# proto_secondaire.net
KiCad netlist of a schematic drawn in EAGLE
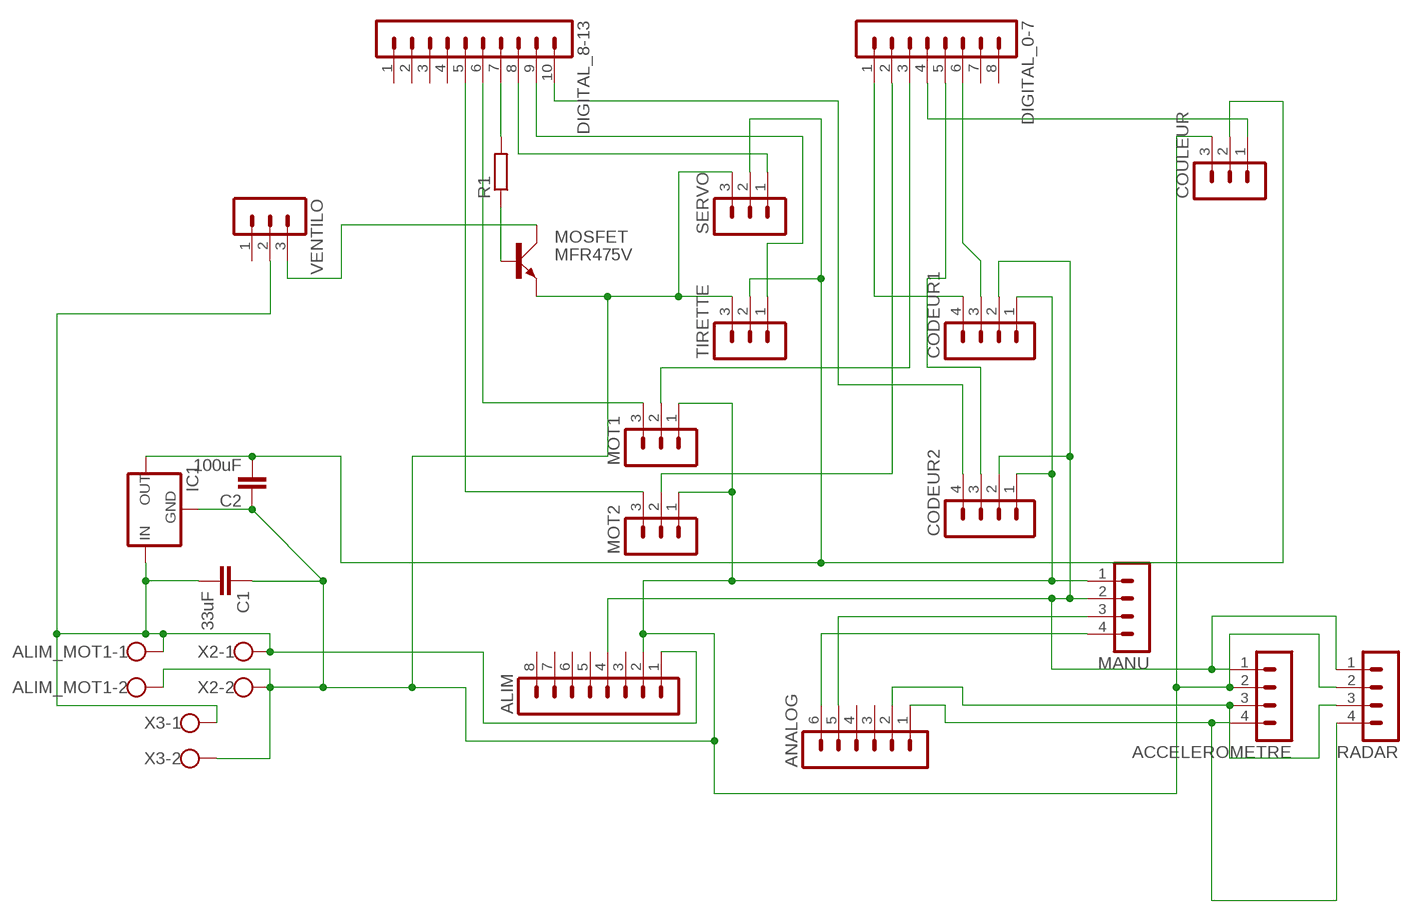
[diagram p0: schematic, sheet 1]

(export (version "E")
  (design (tool "Eeschema 10.0.6"))
  (components
    (comp (ref "ACCELEROMETRE")
      (value "MA04-1")
      (footprint "eagle-import:MA04-1")
      (libsource (lib "eagle-import") (part "MA04-1"))
    )
    (comp (ref "ALIM")
      (value "MA08-1")
      (footprint "eagle-import:MA08-1")
      (libsource (lib "eagle-import") (part "MA08-1"))
    )
    (comp (ref "ALIM_MOT1")
      (value "W237-102")
      (footprint "eagle-import:W237-102")
      (fields (field (name "MPN") "237-102"))
      (libsource (lib "eagle-import") (part "W237-102"))
    )
    (comp (ref "ANALOG")
      (value "MA06-1")
      (footprint "eagle-import:MA06-1")
      (libsource (lib "eagle-import") (part "MA06-1"))
    )
    (comp (ref "C1")
      (value "33uF")
      (footprint "eagle-import:C5B5")
      (libsource (lib "eagle-import") (part "C5/5"))
    )
    (comp (ref "C2")
      (value "100uF")
      (footprint "eagle-import:C5B5")
      (libsource (lib "eagle-import") (part "C5/5"))
    )
    (comp (ref "CODEUR1")
      (value "MA04-1")
      (footprint "eagle-import:MA04-1")
      (libsource (lib "eagle-import") (part "MA04-1"))
    )
    (comp (ref "CODEUR2")
      (value "MA04-1")
      (footprint "eagle-import:MA04-1")
      (libsource (lib "eagle-import") (part "MA04-1"))
    )
    (comp (ref "COULEUR")
      (value "MA03-1")
      (footprint "eagle-import:MA03-1")
      (libsource (lib "eagle-import") (part "MA03-1"))
    )
    (comp (ref "DIGITAL_0-7")
      (value "MA08-1")
      (footprint "eagle-import:MA08-1")
      (libsource (lib "eagle-import") (part "MA08-1"))
    )
    (comp (ref "DIGITAL_8-13")
      (value "MA10-1")
      (footprint "eagle-import:MA10-1")
      (libsource (lib "eagle-import") (part "MA10-1"))
    )
    (comp (ref "IC1")
      (value "78XXS")
      (footprint "eagle-import:78XXS")
      (libsource (lib "eagle-import") (part "78XXS"))
    )
    (comp (ref "MANU")
      (value "MA04-1")
      (footprint "eagle-import:MA04-1")
      (libsource (lib "eagle-import") (part "MA04-1"))
    )
    (comp (ref "MOSFET")
      (value "MFR475V")
      (footprint "eagle-import:TO220AV")
      (libsource (lib "eagle-import") (part "MFR4V75"))
    )
    (comp (ref "MOT1")
      (value "MA03-1")
      (footprint "eagle-import:MA03-1")
      (libsource (lib "eagle-import") (part "MA03-1"))
    )
    (comp (ref "MOT2")
      (value "MA03-1")
      (footprint "eagle-import:MA03-1")
      (libsource (lib "eagle-import") (part "MA03-1"))
    )
    (comp (ref "R1")
      (value "R-EU_0204/5")
      (footprint "eagle-import:0204_5")
      (libsource (lib "eagle-import") (part "R-EU_0204/5"))
    )
    (comp (ref "RADAR")
      (value "MA04-1")
      (footprint "eagle-import:MA04-1")
      (libsource (lib "eagle-import") (part "MA04-1"))
    )
    (comp (ref "SERVO")
      (value "MA03-1")
      (footprint "eagle-import:MA03-1")
      (libsource (lib "eagle-import") (part "MA03-1"))
    )
    (comp (ref "TIRETTE")
      (value "MA03-1")
      (footprint "eagle-import:MA03-1")
      (libsource (lib "eagle-import") (part "MA03-1"))
    )
    (comp (ref "VENTILO")
      (value "MA03-1")
      (footprint "eagle-import:MA03-1")
      (libsource (lib "eagle-import") (part "MA03-1"))
    )
    (comp (ref "X2")
      (value "W237-102")
      (footprint "eagle-import:W237-102")
      (fields (field (name "MPN") "237-102"))
      (libsource (lib "eagle-import") (part "W237-102"))
    )
    (comp (ref "X3")
      (value "W237-102")
      (footprint "eagle-import:W237-102")
      (fields (field (name "MPN") "237-102"))
      (libsource (lib "eagle-import") (part "W237-102"))
    )
  )
  (nets
    (net (code "1") (name "Net-(ACCELEROMETRE-Pad1)") (class "Default")
      (node (ref "ACCELEROMETRE") (pin "1") (pinfunction "1_1") (pintype "passive"))
      (node (ref "ALIM") (pin "4") (pinfunction "4_4") (pintype "passive"))
      (node (ref "CODEUR1") (pin "2") (pinfunction "2_2") (pintype "passive"))
      (node (ref "CODEUR2") (pin "2") (pinfunction "2_2") (pintype "passive"))
      (node (ref "MANU") (pin "2") (pinfunction "2_2") (pintype "passive"))
      (node (ref "RADAR") (pin "1") (pinfunction "1_1") (pintype "passive"))
    )
    (net (code "2") (name "Net-(ACCELEROMETRE-Pad3)") (class "Default")
      (node (ref "ACCELEROMETRE") (pin "3") (pinfunction "3_3") (pintype "passive"))
      (node (ref "ANALOG") (pin "2") (pinfunction "2_2") (pintype "passive"))
      (node (ref "RADAR") (pin "3") (pinfunction "3_3") (pintype "passive"))
    )
    (net (code "3") (name "Net-(ACCELEROMETRE-Pad4)") (class "Default")
      (node (ref "ACCELEROMETRE") (pin "4") (pinfunction "4_4") (pintype "passive"))
      (node (ref "ANALOG") (pin "1") (pinfunction "1_1") (pintype "passive"))
      (node (ref "RADAR") (pin "4") (pinfunction "4_4") (pintype "passive"))
    )
    (net (code "4") (name "Net-(ALIM_MOT1A-KL)") (class "Default")
      (node (ref "ALIM") (pin "1") (pinfunction "1_1") (pintype "passive"))
      (node (ref "ALIM_MOT1") (pin "1") (pinfunction "KL_1") (pintype "passive"))
      (node (ref "C1") (pin "2") (pinfunction "2_2") (pintype "passive"))
      (node (ref "IC1") (pin "IN") (pinfunction "IN_IN") (pintype "input"))
      (node (ref "VENTILO") (pin "2") (pinfunction "2_2") (pintype "passive"))
      (node (ref "X2") (pin "1") (pinfunction "KL_1") (pintype "passive"))
      (node (ref "X3") (pin "1") (pinfunction "KL_1") (pintype "passive"))
    )
    (net (code "5") (name "Net-(ALIM_MOT1B-KL)") (class "Default")
      (node (ref "ACCELEROMETRE") (pin "2") (pinfunction "2_2") (pintype "passive"))
      (node (ref "ALIM") (pin "2") (pinfunction "2_2") (pintype "passive"))
      (node (ref "ALIM_MOT1") (pin "2") (pinfunction "KL_2") (pintype "passive"))
      (node (ref "C1") (pin "1") (pinfunction "1_1") (pintype "passive"))
      (node (ref "C2") (pin "1") (pinfunction "1_1") (pintype "passive"))
      (node (ref "CODEUR1") (pin "1") (pinfunction "1_1") (pintype "passive"))
      (node (ref "CODEUR2") (pin "1") (pinfunction "1_1") (pintype "passive"))
      (node (ref "COULEUR") (pin "3") (pinfunction "3_3") (pintype "passive"))
      (node (ref "IC1") (pin "GND") (pinfunction "GND_GND") (pintype "input"))
      (node (ref "MANU") (pin "1") (pinfunction "1_1") (pintype "passive"))
      (node (ref "MOSFET") (pin "E") (pinfunction "E_E") (pintype "passive"))
      (node (ref "MOT1") (pin "1") (pinfunction "1_1") (pintype "passive"))
      (node (ref "MOT2") (pin "1") (pinfunction "1_1") (pintype "passive"))
      (node (ref "RADAR") (pin "2") (pinfunction "2_2") (pintype "passive"))
      (node (ref "SERVO") (pin "3") (pinfunction "3_3") (pintype "passive"))
      (node (ref "TIRETTE") (pin "3") (pinfunction "3_3") (pintype "passive"))
      (node (ref "X2") (pin "2") (pinfunction "KL_2") (pintype "passive"))
      (node (ref "X3") (pin "2") (pinfunction "KL_2") (pintype "passive"))
    )
    (net (code "6") (name "Net-(ANALOG-Pad5)") (class "Default")
      (node (ref "ANALOG") (pin "5") (pinfunction "5_5") (pintype "passive"))
      (node (ref "MANU") (pin "3") (pinfunction "3_3") (pintype "passive"))
    )
    (net (code "7") (name "Net-(ANALOG-Pad6)") (class "Default")
      (node (ref "ANALOG") (pin "6") (pinfunction "6_6") (pintype "passive"))
      (node (ref "MANU") (pin "4") (pinfunction "4_4") (pintype "passive"))
    )
    (net (code "8") (name "Net-(C2-Pad2)") (class "Default")
      (node (ref "C2") (pin "2") (pinfunction "2_2") (pintype "passive"))
      (node (ref "COULEUR") (pin "2") (pinfunction "2_2") (pintype "passive"))
      (node (ref "IC1") (pin "OUT") (pinfunction "OUT_OUT") (pintype "passive"))
      (node (ref "SERVO") (pin "2") (pinfunction "2_2") (pintype "passive"))
      (node (ref "TIRETTE") (pin "2") (pinfunction "2_2") (pintype "passive"))
    )
    (net (code "9") (name "Net-(CODEUR1-Pad3)") (class "Default")
      (node (ref "CODEUR1") (pin "3") (pinfunction "3_3") (pintype "passive"))
      (node (ref "DIGITAL_0-7") (pin "6") (pinfunction "6_6") (pintype "passive"))
    )
    (net (code "10") (name "Net-(CODEUR1-Pad4)") (class "Default")
      (node (ref "CODEUR1") (pin "4") (pinfunction "4_4") (pintype "passive"))
      (node (ref "DIGITAL_0-7") (pin "1") (pinfunction "1_1") (pintype "passive"))
    )
    (net (code "11") (name "Net-(CODEUR2-Pad3)") (class "Default")
      (node (ref "CODEUR2") (pin "3") (pinfunction "3_3") (pintype "passive"))
      (node (ref "DIGITAL_0-7") (pin "5") (pinfunction "5_5") (pintype "passive"))
    )
    (net (code "12") (name "Net-(CODEUR2-Pad4)") (class "Default")
      (node (ref "CODEUR2") (pin "4") (pinfunction "4_4") (pintype "passive"))
      (node (ref "DIGITAL_8-13") (pin "10") (pinfunction "10_10") (pintype "passive"))
    )
    (net (code "13") (name "Net-(COULEUR-Pad1)") (class "Default")
      (node (ref "COULEUR") (pin "1") (pinfunction "1_1") (pintype "passive"))
      (node (ref "DIGITAL_0-7") (pin "4") (pinfunction "4_4") (pintype "passive"))
    )
    (net (code "14") (name "Net-(DIGITAL_0-7-Pad2)") (class "Default")
      (node (ref "DIGITAL_0-7") (pin "2") (pinfunction "2_2") (pintype "passive"))
      (node (ref "MOT2") (pin "2") (pinfunction "2_2") (pintype "passive"))
    )
    (net (code "15") (name "Net-(DIGITAL_0-7-Pad3)") (class "Default")
      (node (ref "DIGITAL_0-7") (pin "3") (pinfunction "3_3") (pintype "passive"))
      (node (ref "MOT1") (pin "2") (pinfunction "2_2") (pintype "passive"))
    )
    (net (code "16") (name "Net-(DIGITAL_8-13-Pad5)") (class "Default")
      (node (ref "DIGITAL_8-13") (pin "5") (pinfunction "5_5") (pintype "passive"))
      (node (ref "MOT2") (pin "3") (pinfunction "3_3") (pintype "passive"))
    )
    (net (code "17") (name "Net-(DIGITAL_8-13-Pad6)") (class "Default")
      (node (ref "DIGITAL_8-13") (pin "6") (pinfunction "6_6") (pintype "passive"))
      (node (ref "MOT1") (pin "3") (pinfunction "3_3") (pintype "passive"))
    )
    (net (code "18") (name "Net-(DIGITAL_8-13-Pad7)") (class "Default")
      (node (ref "DIGITAL_8-13") (pin "7") (pinfunction "7_7") (pintype "passive"))
      (node (ref "R1") (pin "2") (pinfunction "2_2") (pintype "passive"))
    )
    (net (code "19") (name "Net-(DIGITAL_8-13-Pad8)") (class "Default")
      (node (ref "DIGITAL_8-13") (pin "8") (pinfunction "8_8") (pintype "passive"))
      (node (ref "SERVO") (pin "1") (pinfunction "1_1") (pintype "passive"))
    )
    (net (code "20") (name "Net-(DIGITAL_8-13-Pad9)") (class "Default")
      (node (ref "DIGITAL_8-13") (pin "9") (pinfunction "9_9") (pintype "passive"))
      (node (ref "TIRETTE") (pin "1") (pinfunction "1_1") (pintype "passive"))
    )
    (net (code "21") (name "Net-(MOSFET-PadB)") (class "Default")
      (node (ref "MOSFET") (pin "B") (pinfunction "B_B") (pintype "passive"))
      (node (ref "R1") (pin "1") (pinfunction "1_1") (pintype "passive"))
    )
    (net (code "22") (name "Net-(MOSFET-PadC)") (class "Default")
      (node (ref "MOSFET") (pin "C") (pinfunction "C_C") (pintype "passive"))
      (node (ref "VENTILO") (pin "3") (pinfunction "3_3") (pintype "passive"))
    )
    (net (code "23") (name "unconnected-(ALIM-Pad3)") (class "Default")
      (node (ref "ALIM") (pin "3") (pinfunction "3_3") (pintype "passive"))
    )
    (net (code "24") (name "unconnected-(ALIM-Pad5)") (class "Default")
      (node (ref "ALIM") (pin "5") (pinfunction "5_5") (pintype "passive"))
    )
    (net (code "25") (name "unconnected-(ALIM-Pad6)") (class "Default")
      (node (ref "ALIM") (pin "6") (pinfunction "6_6") (pintype "passive"))
    )
    (net (code "26") (name "unconnected-(ALIM-Pad7)") (class "Default")
      (node (ref "ALIM") (pin "7") (pinfunction "7_7") (pintype "passive"))
    )
    (net (code "27") (name "unconnected-(ALIM-Pad8)") (class "Default")
      (node (ref "ALIM") (pin "8") (pinfunction "8_8") (pintype "passive"))
    )
    (net (code "28") (name "unconnected-(ANALOG-Pad3)") (class "Default")
      (node (ref "ANALOG") (pin "3") (pinfunction "3_3") (pintype "passive"))
    )
    (net (code "29") (name "unconnected-(ANALOG-Pad4)") (class "Default")
      (node (ref "ANALOG") (pin "4") (pinfunction "4_4") (pintype "passive"))
    )
    (net (code "30") (name "unconnected-(DIGITAL_0-7-Pad7)") (class "Default")
      (node (ref "DIGITAL_0-7") (pin "7") (pinfunction "7_7") (pintype "passive"))
    )
    (net (code "31") (name "unconnected-(DIGITAL_0-7-Pad8)") (class "Default")
      (node (ref "DIGITAL_0-7") (pin "8") (pinfunction "8_8") (pintype "passive"))
    )
    (net (code "32") (name "unconnected-(DIGITAL_8-13-Pad1)") (class "Default")
      (node (ref "DIGITAL_8-13") (pin "1") (pinfunction "1_1") (pintype "passive"))
    )
    (net (code "33") (name "unconnected-(DIGITAL_8-13-Pad2)") (class "Default")
      (node (ref "DIGITAL_8-13") (pin "2") (pinfunction "2_2") (pintype "passive"))
    )
    (net (code "34") (name "unconnected-(DIGITAL_8-13-Pad3)") (class "Default")
      (node (ref "DIGITAL_8-13") (pin "3") (pinfunction "3_3") (pintype "passive"))
    )
    (net (code "35") (name "unconnected-(DIGITAL_8-13-Pad4)") (class "Default")
      (node (ref "DIGITAL_8-13") (pin "4") (pinfunction "4_4") (pintype "passive"))
    )
    (net (code "36") (name "unconnected-(VENTILO-Pad1)") (class "Default")
      (node (ref "VENTILO") (pin "1") (pinfunction "1_1") (pintype "passive"))
    )
  )
)
